# Super-Regenerative-FM-KosmosX3000.net
KiCad netlist of a schematic drawn in EAGLE
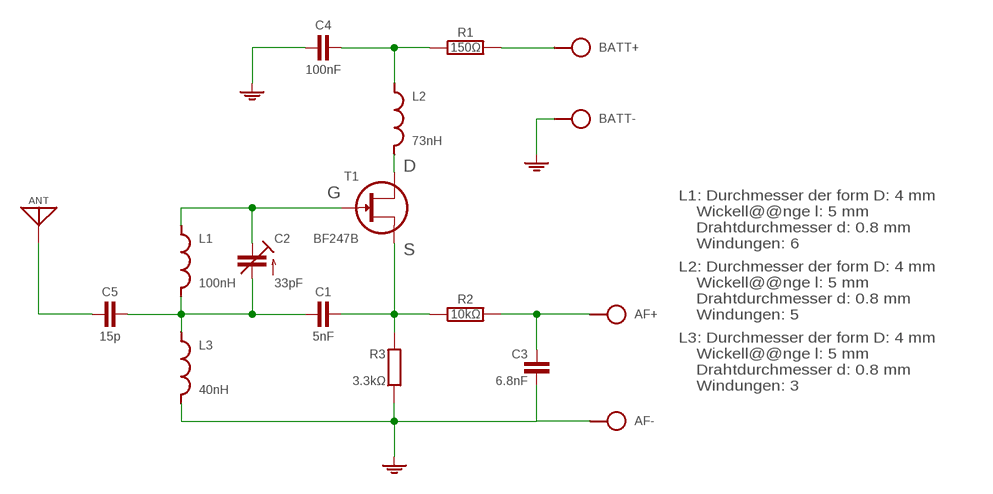
[diagram p0: schematic, sheet 1]

(export (version "E")
  (design (tool "Eeschema 10.0.6"))
  (components
    (comp (ref "AF")
      (value "SPAD+-+-")
      (footprint "eagle-import:SPAD+-")
      (libsource (lib "eagle-import") (part "SPAD+-+-"))
    )
    (comp (ref "ANT")
      (value "ANT")
      (footprint "eagle-import:SPAD")
      (libsource (lib "eagle-import") (part "ANT"))
    )
    (comp (ref "BATT")
      (value "SPAD+--+")
      (footprint "eagle-import:SPAD-+")
      (libsource (lib "eagle-import") (part "SPAD+--+"))
    )
    (comp (ref "C1")
      (value "5nF")
      (footprint "eagle-import:C050-020X044")
      (libsource (lib "eagle-import") (part "C050-020X044"))
    )
    (comp (ref "C2")
      (value "33pF")
      (footprint "eagle-import:TRIM-2222-808")
      (libsource (lib "eagle-import") (part "C-TR-PH201272222-808-2PIN"))
    )
    (comp (ref "C3")
      (value "6.8nF")
      (footprint "eagle-import:C050-020X044")
      (libsource (lib "eagle-import") (part "C050-020X044"))
    )
    (comp (ref "C4")
      (value "100nF")
      (footprint "eagle-import:C050-020X044")
      (libsource (lib "eagle-import") (part "C050-020X044"))
    )
    (comp (ref "C5")
      (value "15p")
      (footprint "eagle-import:C025-015X024")
      (libsource (lib "eagle-import") (part "C025-015X024"))
    )
    (comp (ref "L1")
      (value "100nH")
      (footprint "eagle-import:L-04-5_6V-C")
      (libsource (lib "eagle-import") (part "L-SHORT04-5/5V-C"))
    )
    (comp (ref "L2")
      (value "73nH")
      (footprint "eagle-import:L-04-5_6V-C")
      (libsource (lib "eagle-import") (part "L-SHORT04-5/5V-C"))
    )
    (comp (ref "L3")
      (value "40nH")
      (footprint "eagle-import:L-04-5_6V-C")
      (libsource (lib "eagle-import") (part "L-SHORT04-5/5V-C"))
    )
    (comp (ref "R1")
      (value "150Ω")
      (footprint "eagle-import:0204_15-V")
      (libsource (lib "eagle-import") (part "R-H0204/15-V"))
    )
    (comp (ref "R2")
      (value "10kΩ")
      (footprint "eagle-import:0204_10-V")
      (libsource (lib "eagle-import") (part "R-H0204/10-V"))
    )
    (comp (ref "R3")
      (value "3.3kΩ")
      (footprint "eagle-import:0204_10-V")
      (libsource (lib "eagle-import") (part "R0204/10-V"))
    )
    (comp (ref "T1")
      (value "BF247B")
      (footprint "eagle-import:TO92")
      (libsource (lib "eagle-import") (part "BF247B"))
    )
  )
  (nets
    (net (code "1") (name "GND") (class "Default")
      (node (ref "AF") (pin "1") (pinfunction "P$1_1") (pintype "passive"))
      (node (ref "BATT") (pin "1") (pinfunction "P$1_1") (pintype "passive"))
      (node (ref "C3") (pin "2") (pinfunction "2_2") (pintype "passive"))
      (node (ref "C4") (pin "2") (pinfunction "2_2") (pintype "passive"))
      (node (ref "L3") (pin "1") (pinfunction "1_1") (pintype "passive"))
      (node (ref "R3") (pin "2") (pinfunction "1_2") (pintype "passive"))
    )
    (net (code "2") (name "Net-(AFA-P$1)") (class "Default")
      (node (ref "AF") (pin "2") (pinfunction "P$1_2") (pintype "passive"))
      (node (ref "C3") (pin "1") (pinfunction "1_1") (pintype "passive"))
      (node (ref "R2") (pin "2") (pinfunction "2_2") (pintype "passive"))
    )
    (net (code "3") (name "Net-(ANT-Pad1)") (class "Default")
      (node (ref "ANT") (pin "1") (pinfunction "1_1") (pintype "output"))
      (node (ref "C5") (pin "2") (pinfunction "2_2") (pintype "passive"))
    )
    (net (code "4") (name "Net-(BATTA-P$1)") (class "Default")
      (node (ref "BATT") (pin "2") (pinfunction "P$1_2") (pintype "passive"))
      (node (ref "R1") (pin "2") (pinfunction "2_2") (pintype "passive"))
    )
    (net (code "5") (name "Net-(C2-A)") (class "Default")
      (node (ref "C1") (pin "2") (pinfunction "2_2") (pintype "passive"))
      (node (ref "C2") (pin "2") (pinfunction "A_2") (pintype "passive"))
      (node (ref "C5") (pin "1") (pinfunction "1_1") (pintype "passive"))
      (node (ref "L1") (pin "1") (pinfunction "1_1") (pintype "passive"))
      (node (ref "L3") (pin "2") (pinfunction "2_2") (pintype "passive"))
    )
    (net (code "6") (name "Net-(C2-E)") (class "Default")
      (node (ref "C2") (pin "1") (pinfunction "E_1") (pintype "passive"))
      (node (ref "L1") (pin "2") (pinfunction "2_2") (pintype "passive"))
      (node (ref "T1") (pin "3") (pinfunction "G_3") (pintype "passive"))
    )
    (net (code "7") (name "Net-(C4-Pad1)") (class "Default")
      (node (ref "C4") (pin "1") (pinfunction "1_1") (pintype "passive"))
      (node (ref "L2") (pin "2") (pinfunction "2_2") (pintype "passive"))
      (node (ref "R1") (pin "1") (pinfunction "1_1") (pintype "passive"))
    )
    (net (code "8") (name "Net-(R3-2)") (class "Default")
      (node (ref "C1") (pin "1") (pinfunction "1_1") (pintype "passive"))
      (node (ref "R2") (pin "1") (pinfunction "1_1") (pintype "passive"))
      (node (ref "R3") (pin "1") (pinfunction "2_1") (pintype "passive"))
      (node (ref "T1") (pin "2") (pinfunction "S_2") (pintype "passive"))
    )
    (net (code "9") (name "Net-(T1-D)") (class "Default")
      (node (ref "L2") (pin "1") (pinfunction "1_1") (pintype "passive"))
      (node (ref "T1") (pin "1") (pinfunction "D_1") (pintype "passive"))
    )
  )
)
